# transmitter.net
KiCad netlist of a schematic drawn in Altium Designer
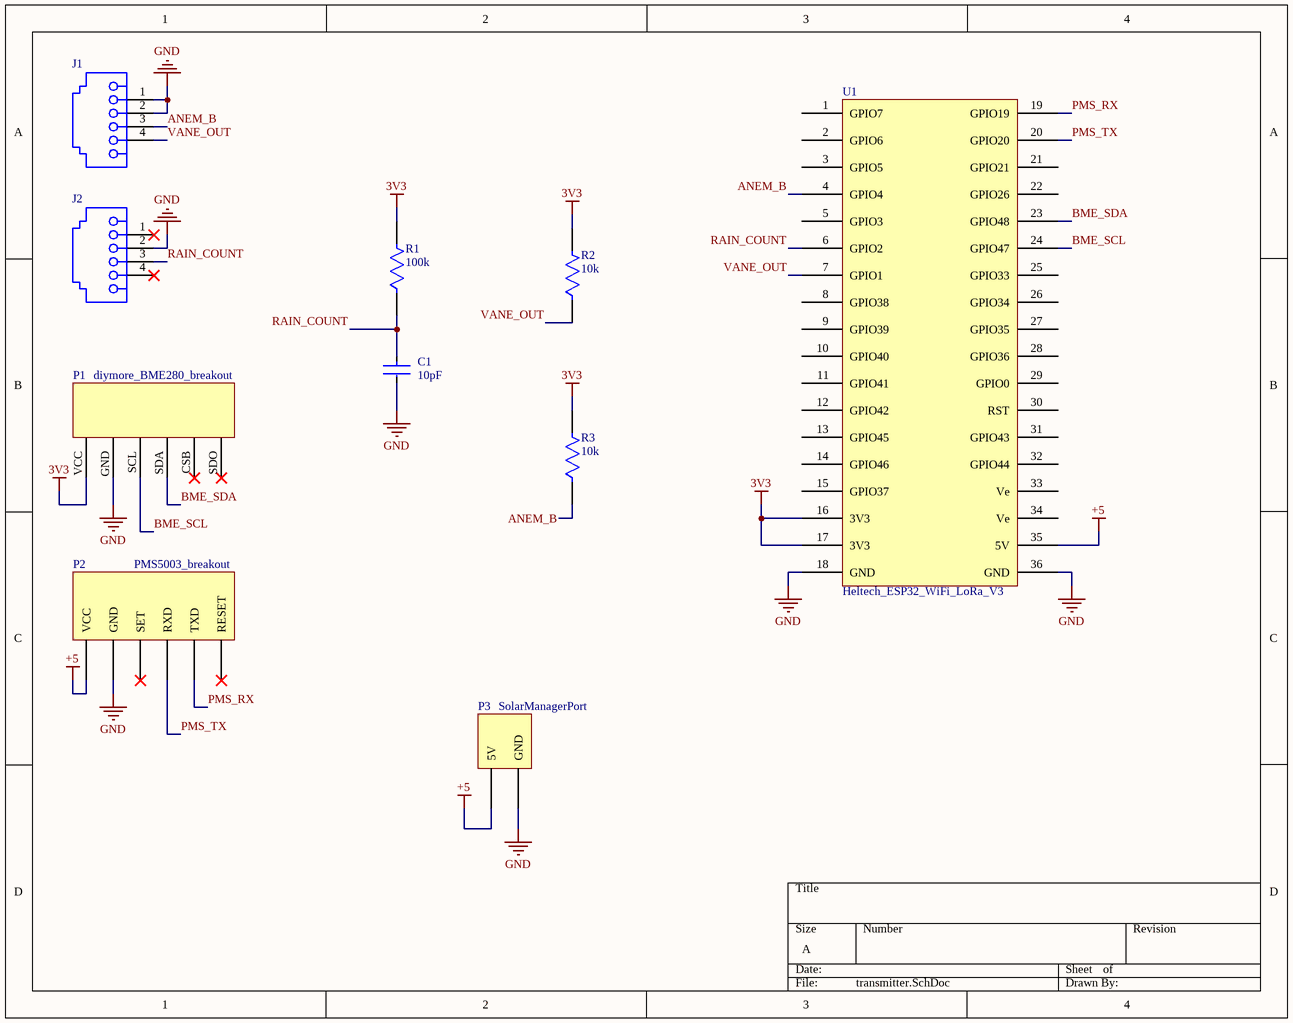
[diagram p0: transmitter.SchDoc]

(export (version "E")
  (design (tool "Eeschema 10.0.6"))
  (components
    (comp (ref "C1")
      (value "VY2103M63Y5US63V7")
      (footprint "FP-VY2103M63Y5US63V7-MFG")
      (description "CAP CER 10000PF 440VAC Y5U RDL")
      (fields (field (name "TOLERANCE") "20%") (field (name "CAPACITANCE") "10pF"))
      (libsource (lib "Altium Content Vault") (part "1c05c9fa918bfedca311cc83546bad0"))
    )
    (comp (ref "J1")
      (value "615004144121")
      (footprint "615004144121")
      (libsource (lib "Altium Content Vault") (part "6P4C - 1 Port - Un-Shielded"))
    )
    (comp (ref "J2")
      (value "615004144121")
      (footprint "615004144121")
      (libsource (lib "Altium Content Vault") (part "6P4C - 1 Port - Un-Shielded"))
    )
    (comp (ref "P1")
      (value "diymore_BME280_breakout")
      (footprint "PCBComponent_1")
      (libsource (lib "diymore_BME280_breakout") (part "diymore_BME280_breakout"))
    )
    (comp (ref "P2")
      (value "PMS5003_breakout")
      (footprint "PCBComponent_1")
      (libsource (lib "Altium_PMS5003_Library") (part "PMS5003_breakout"))
    )
    (comp (ref "P3")
      (value "SolarManagerPort")
      (footprint "PCBComponent_1")
      (libsource (lib "SolarManagerPort") (part "Component_1"))
    )
    (comp (ref "R1")
      (value "MRS25000C1002FCT00")
      (footprint "FP-MRS25-MFG")
      (fields (field (name "RESISTANCE") "100k") (field (name "TOLERANCE") "1%"))
      (libsource (lib "Altium Content Vault") (part "1029c3af85768c4190bb7ad29bc67b5"))
    )
    (comp (ref "R2")
      (value "MRS25000C1002FCT00")
      (footprint "FP-MRS25-MFG")
      (fields (field (name "RESISTANCE") "10k") (field (name "TOLERANCE") "1%"))
      (libsource (lib "Altium Content Vault") (part "1029c3af85768c4190bb7ad29bc67b5"))
    )
    (comp (ref "R3")
      (value "MRS25000C1002FCT00")
      (footprint "FP-MRS25-MFG")
      (fields (field (name "RESISTANCE") "10k") (field (name "TOLERANCE") "1%"))
      (libsource (lib "Altium Content Vault") (part "1029c3af85768c4190bb7ad29bc67b5"))
    )
    (comp (ref "U1")
      (value "Heltech_ESP32_WiFi_LoRa_V3")
      (footprint "PCBComponent_1")
      (libsource (lib "Heltec_WiFi_LoRa_32_V3") (part "Heltech_ESP32_WiFi_LoRa_V3"))
    )
  )
  (nets
    (net (code "1") (name "+5") (class "Default")
      (node (ref "P2") (pin "VCC") (pinfunction "VCC_VCC") (pintype "passive"))
      (node (ref "P3") (pin "5V") (pinfunction "5V_5V") (pintype "passive"))
      (node (ref "U1") (pin "35") (pinfunction "5V_35") (pintype "passive"))
    )
    (net (code "2") (name "/ANEM_B") (class "Default")
      (node (ref "J1") (pin "3") (pinfunction "3_3") (pintype "passive"))
      (node (ref "R3") (pin "1") (pinfunction "1_1") (pintype "passive"))
      (node (ref "U1") (pin "4") (pinfunction "GPIO4_4") (pintype "passive"))
    )
    (net (code "3") (name "/BME_SCL") (class "Default")
      (node (ref "P1") (pin "SCL") (pinfunction "SCL_SCL") (pintype "passive"))
      (node (ref "U1") (pin "24") (pinfunction "GPIO47_24") (pintype "passive"))
    )
    (net (code "4") (name "/BME_SDA") (class "Default")
      (node (ref "P1") (pin "SDA") (pinfunction "SDA_SDA") (pintype "passive"))
      (node (ref "U1") (pin "23") (pinfunction "GPIO48_23") (pintype "passive"))
    )
    (net (code "5") (name "/PMS_RX") (class "Default")
      (node (ref "P2") (pin "TXD") (pinfunction "TXD_TXD") (pintype "passive"))
      (node (ref "U1") (pin "19") (pinfunction "GPIO19_19") (pintype "passive"))
    )
    (net (code "6") (name "/PMS_TX") (class "Default")
      (node (ref "P2") (pin "RXD") (pinfunction "RXD_RXD") (pintype "passive"))
      (node (ref "U1") (pin "20") (pinfunction "GPIO20_20") (pintype "passive"))
    )
    (net (code "7") (name "/RAIN_COUNT") (class "Default")
      (node (ref "C1") (pin "1") (pinfunction "1_1") (pintype "passive"))
      (node (ref "J2") (pin "3") (pinfunction "3_3") (pintype "passive"))
      (node (ref "R1") (pin "1") (pinfunction "1_1") (pintype "passive"))
      (node (ref "U1") (pin "6") (pinfunction "GPIO2_6") (pintype "passive"))
    )
    (net (code "8") (name "/VANE_OUT") (class "Default")
      (node (ref "J1") (pin "4") (pinfunction "4_4") (pintype "passive"))
      (node (ref "R2") (pin "1") (pinfunction "1_1") (pintype "passive"))
      (node (ref "U1") (pin "7") (pinfunction "GPIO1_7") (pintype "passive"))
    )
    (net (code "9") (name "3V3") (class "Default")
      (node (ref "P1") (pin "VCC") (pinfunction "VCC_VCC") (pintype "passive"))
      (node (ref "R1") (pin "2") (pinfunction "2_2") (pintype "passive"))
      (node (ref "R2") (pin "2") (pinfunction "2_2") (pintype "passive"))
      (node (ref "R3") (pin "2") (pinfunction "2_2") (pintype "passive"))
      (node (ref "U1") (pin "16") (pinfunction "3V3_16") (pintype "passive"))
      (node (ref "U1") (pin "17") (pinfunction "3V3_17") (pintype "passive"))
    )
    (net (code "10") (name "GND") (class "Default")
      (node (ref "C1") (pin "2") (pinfunction "2_2") (pintype "passive"))
      (node (ref "J1") (pin "1") (pinfunction "1_1") (pintype "passive"))
      (node (ref "J1") (pin "2") (pinfunction "2_2") (pintype "passive"))
      (node (ref "J2") (pin "2") (pinfunction "2_2") (pintype "passive"))
      (node (ref "P1") (pin "GND") (pinfunction "GND_GND") (pintype "passive"))
      (node (ref "P2") (pin "GND") (pinfunction "GND_GND") (pintype "passive"))
      (node (ref "P3") (pin "GND") (pinfunction "GND_GND") (pintype "passive"))
      (node (ref "U1") (pin "18") (pinfunction "GND_18") (pintype "passive"))
      (node (ref "U1") (pin "36") (pinfunction "GND_36") (pintype "passive"))
    )
    (net (code "11") (name "unconnected-(J2-Pad1)") (class "Default")
      (node (ref "J2") (pin "1") (pinfunction "1_1") (pintype "passive+no_connect"))
    )
    (net (code "12") (name "unconnected-(J2-Pad4)") (class "Default")
      (node (ref "J2") (pin "4") (pinfunction "4_4") (pintype "passive+no_connect"))
    )
    (net (code "13") (name "unconnected-(P1-PadCSB)") (class "Default")
      (node (ref "P1") (pin "CSB") (pinfunction "CSB_CSB") (pintype "passive+no_connect"))
    )
    (net (code "14") (name "unconnected-(P1-PadSDO)") (class "Default")
      (node (ref "P1") (pin "SDO") (pinfunction "SDO_SDO") (pintype "passive+no_connect"))
    )
    (net (code "15") (name "unconnected-(P2-PadRESET)") (class "Default")
      (node (ref "P2") (pin "RESET") (pinfunction "RESET_RESET") (pintype "passive+no_connect"))
    )
    (net (code "16") (name "unconnected-(P2-PadSET)") (class "Default")
      (node (ref "P2") (pin "SET") (pinfunction "SET_SET") (pintype "passive+no_connect"))
    )
    (net (code "17") (name "unconnected-(U1-GPIO0-Pad29)") (class "Default")
      (node (ref "U1") (pin "29") (pinfunction "GPIO0_29") (pintype "passive"))
    )
    (net (code "18") (name "unconnected-(U1-GPIO3-Pad5)") (class "Default")
      (node (ref "U1") (pin "5") (pinfunction "GPIO3_5") (pintype "passive"))
    )
    (net (code "19") (name "unconnected-(U1-GPIO5-Pad3)") (class "Default")
      (node (ref "U1") (pin "3") (pinfunction "GPIO5_3") (pintype "passive"))
    )
    (net (code "20") (name "unconnected-(U1-GPIO6-Pad2)") (class "Default")
      (node (ref "U1") (pin "2") (pinfunction "GPIO6_2") (pintype "passive"))
    )
    (net (code "21") (name "unconnected-(U1-GPIO7-Pad1)") (class "Default")
      (node (ref "U1") (pin "1") (pinfunction "GPIO7_1") (pintype "passive"))
    )
    (net (code "22") (name "unconnected-(U1-GPIO21-Pad21)") (class "Default")
      (node (ref "U1") (pin "21") (pinfunction "GPIO21_21") (pintype "passive"))
    )
    (net (code "23") (name "unconnected-(U1-GPIO26-Pad22)") (class "Default")
      (node (ref "U1") (pin "22") (pinfunction "GPIO26_22") (pintype "passive"))
    )
    (net (code "24") (name "unconnected-(U1-GPIO33-Pad25)") (class "Default")
      (node (ref "U1") (pin "25") (pinfunction "GPIO33_25") (pintype "passive"))
    )
    (net (code "25") (name "unconnected-(U1-GPIO34-Pad26)") (class "Default")
      (node (ref "U1") (pin "26") (pinfunction "GPIO34_26") (pintype "passive"))
    )
    (net (code "26") (name "unconnected-(U1-GPIO35-Pad27)") (class "Default")
      (node (ref "U1") (pin "27") (pinfunction "GPIO35_27") (pintype "passive"))
    )
    (net (code "27") (name "unconnected-(U1-GPIO36-Pad28)") (class "Default")
      (node (ref "U1") (pin "28") (pinfunction "GPIO36_28") (pintype "passive"))
    )
    (net (code "28") (name "unconnected-(U1-GPIO37-Pad15)") (class "Default")
      (node (ref "U1") (pin "15") (pinfunction "GPIO37_15") (pintype "passive"))
    )
    (net (code "29") (name "unconnected-(U1-GPIO38-Pad8)") (class "Default")
      (node (ref "U1") (pin "8") (pinfunction "GPIO38_8") (pintype "passive"))
    )
    (net (code "30") (name "unconnected-(U1-GPIO39-Pad9)") (class "Default")
      (node (ref "U1") (pin "9") (pinfunction "GPIO39_9") (pintype "passive"))
    )
    (net (code "31") (name "unconnected-(U1-GPIO40-Pad10)") (class "Default")
      (node (ref "U1") (pin "10") (pinfunction "GPIO40_10") (pintype "passive"))
    )
    (net (code "32") (name "unconnected-(U1-GPIO41-Pad11)") (class "Default")
      (node (ref "U1") (pin "11") (pinfunction "GPIO41_11") (pintype "passive"))
    )
    (net (code "33") (name "unconnected-(U1-GPIO42-Pad12)") (class "Default")
      (node (ref "U1") (pin "12") (pinfunction "GPIO42_12") (pintype "passive"))
    )
    (net (code "34") (name "unconnected-(U1-GPIO43-Pad31)") (class "Default")
      (node (ref "U1") (pin "31") (pinfunction "GPIO43_31") (pintype "passive"))
    )
    (net (code "35") (name "unconnected-(U1-GPIO44-Pad32)") (class "Default")
      (node (ref "U1") (pin "32") (pinfunction "GPIO44_32") (pintype "passive"))
    )
    (net (code "36") (name "unconnected-(U1-GPIO45-Pad13)") (class "Default")
      (node (ref "U1") (pin "13") (pinfunction "GPIO45_13") (pintype "passive"))
    )
    (net (code "37") (name "unconnected-(U1-GPIO46-Pad14)") (class "Default")
      (node (ref "U1") (pin "14") (pinfunction "GPIO46_14") (pintype "passive"))
    )
    (net (code "38") (name "unconnected-(U1-RST-Pad30)") (class "Default")
      (node (ref "U1") (pin "30") (pinfunction "RST_30") (pintype "passive"))
    )
    (net (code "39") (name "unconnected-(U1-Ve-Pad33)") (class "Default")
      (node (ref "U1") (pin "33") (pinfunction "Ve_33") (pintype "passive"))
    )
    (net (code "40") (name "unconnected-(U1-Ve-Pad34)") (class "Default")
      (node (ref "U1") (pin "34") (pinfunction "Ve_34") (pintype "passive"))
    )
  )
)
